# Driver_Message_Board.net
KiCad netlist of a schematic drawn in EAGLE
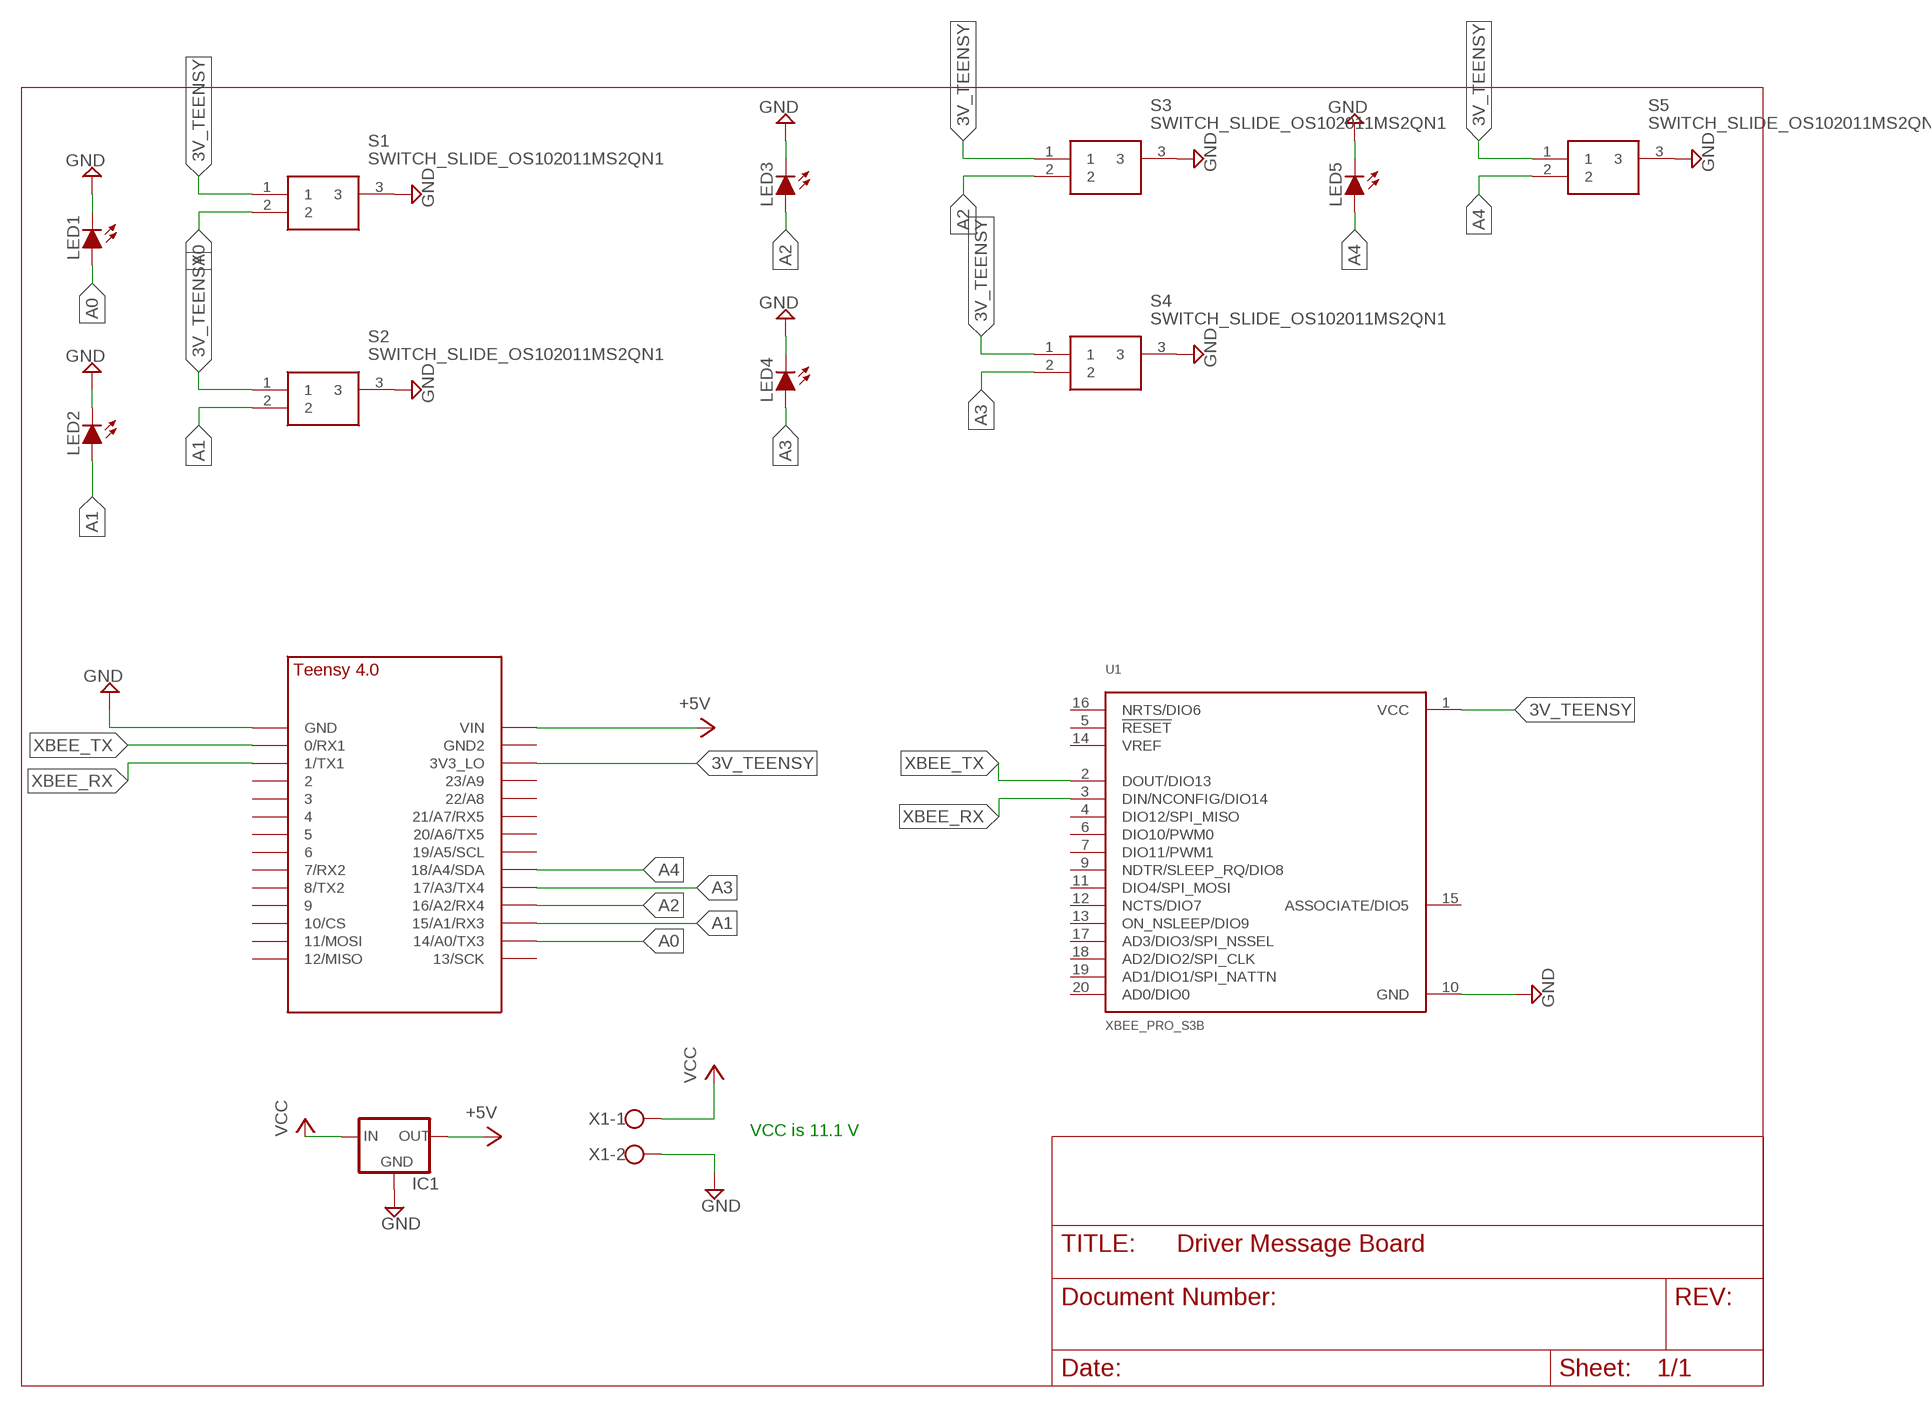
[diagram p0: schematic, sheet 1]

(export (version "E")
  (design (tool "Eeschema 10.0.6"))
  (components
    (comp (ref "IC1")
      (value "REG_5V_L7805_HOR_HOLE")
      (footprint "eagle-import:TO-220-H-HOLE")
      (libsource (lib "eagle-import") (part "REG_5V_L7805_HOR_HOLE"))
    )
    (comp (ref "LED1")
      (value "LED-5MM")
      (footprint "eagle-import:LED-5MM")
      (libsource (lib "eagle-import") (part "LED-5MM"))
    )
    (comp (ref "LED2")
      (value "LED-5MM")
      (footprint "eagle-import:LED-5MM")
      (libsource (lib "eagle-import") (part "LED-5MM"))
    )
    (comp (ref "LED3")
      (value "LED-5MM")
      (footprint "eagle-import:LED-5MM")
      (libsource (lib "eagle-import") (part "LED-5MM"))
    )
    (comp (ref "LED4")
      (value "LED-5MM")
      (footprint "eagle-import:LED-5MM")
      (libsource (lib "eagle-import") (part "LED-5MM"))
    )
    (comp (ref "LED5")
      (value "LED-5MM")
      (footprint "eagle-import:LED-5MM")
      (libsource (lib "eagle-import") (part "LED-5MM"))
    )
    (comp (ref "S1")
      (value "SWITCH_SLIDE_OS102011MS2QN1")
      (footprint "eagle-import:OS102011MA1QN1")
      (fields
        (field (name "ARROW_PART_NUMBER") "OS102011MS2QN1")
        (field (name "MOUSER_PART_NUMBER") "611-OS102011MS2QN1")
      )
      (libsource (lib "eagle-import") (part "SWITCH_SLIDE_OS102011MS2QN1"))
    )
    (comp (ref "S2")
      (value "SWITCH_SLIDE_OS102011MS2QN1")
      (footprint "eagle-import:OS102011MA1QN1")
      (fields
        (field (name "ARROW_PART_NUMBER") "OS102011MS2QN1")
        (field (name "MOUSER_PART_NUMBER") "611-OS102011MS2QN1")
      )
      (libsource (lib "eagle-import") (part "SWITCH_SLIDE_OS102011MS2QN1"))
    )
    (comp (ref "S3")
      (value "SWITCH_SLIDE_OS102011MS2QN1")
      (footprint "eagle-import:OS102011MA1QN1")
      (fields
        (field (name "ARROW_PART_NUMBER") "OS102011MS2QN1")
        (field (name "MOUSER_PART_NUMBER") "611-OS102011MS2QN1")
      )
      (libsource (lib "eagle-import") (part "SWITCH_SLIDE_OS102011MS2QN1"))
    )
    (comp (ref "S4")
      (value "SWITCH_SLIDE_OS102011MS2QN1")
      (footprint "eagle-import:OS102011MA1QN1")
      (fields
        (field (name "ARROW_PART_NUMBER") "OS102011MS2QN1")
        (field (name "MOUSER_PART_NUMBER") "611-OS102011MS2QN1")
      )
      (libsource (lib "eagle-import") (part "SWITCH_SLIDE_OS102011MS2QN1"))
    )
    (comp (ref "S5")
      (value "SWITCH_SLIDE_OS102011MS2QN1")
      (footprint "eagle-import:OS102011MA1QN1")
      (fields
        (field (name "ARROW_PART_NUMBER") "OS102011MS2QN1")
        (field (name "MOUSER_PART_NUMBER") "611-OS102011MS2QN1")
      )
      (libsource (lib "eagle-import") (part "SWITCH_SLIDE_OS102011MS2QN1"))
    )
    (comp (ref "U$1")
      (value "TEENSY_4.0_SIMPLE")
      (footprint "eagle-import:TEENSY_4.0_SIMPLE")
      (libsource (lib "eagle-import") (part "TEENSY_4.0_SIMPLE"))
    )
    (comp (ref "U1")
      (value "XBEE_PRO_S3B")
      (footprint "eagle-import:XBEE_PRO_S3B")
      (fields
        (field (name "DIGI-KEY_PART_NUMBER") "602-1293-ND")
        (field (name "MF") "Digi International")
        (field (name "MP") "XBP9B-XCST-001")
      )
      (libsource (lib "eagle-import") (part "XBEE_PRO_S3B"))
    )
    (comp (ref "X1")
      (value "W237-102")
      (footprint "eagle-import:W237-102")
      (fields (field (name "MPN") "237-102"))
      (libsource (lib "eagle-import") (part "W237-102"))
    )
  )
  (nets
    (net (code "1") (name "+5V") (class "Default")
      (node (ref "IC1") (pin "3") (pinfunction "OUT_3") (pintype "output"))
      (node (ref "U$1") (pin "VIN") (pinfunction "VIN_VIN") (pintype "bidirectional"))
    )
    (net (code "2") (name "3V_TEENSY") (class "Default")
      (node (ref "S1") (pin "1") (pinfunction "1_1") (pintype "bidirectional"))
      (node (ref "S2") (pin "1") (pinfunction "1_1") (pintype "bidirectional"))
      (node (ref "S3") (pin "1") (pinfunction "1_1") (pintype "bidirectional"))
      (node (ref "S4") (pin "1") (pinfunction "1_1") (pintype "bidirectional"))
      (node (ref "S5") (pin "1") (pinfunction "1_1") (pintype "bidirectional"))
      (node (ref "U$1") (pin "3V3_LO") (pinfunction "3V3_LO_3V3_LO") (pintype "bidirectional"))
      (node (ref "U1") (pin "1") (pinfunction "VCC_1") (pintype "power_in"))
    )
    (net (code "3") (name "A0") (class "Default")
      (node (ref "LED1") (pin "A") (pinfunction "A_A") (pintype "passive"))
      (node (ref "S1") (pin "2") (pinfunction "2_2") (pintype "bidirectional"))
      (node (ref "U$1") (pin "14/A0") (pinfunction "14/A0/TX3_14/A0") (pintype "bidirectional"))
    )
    (net (code "4") (name "A1") (class "Default")
      (node (ref "LED2") (pin "A") (pinfunction "A_A") (pintype "passive"))
      (node (ref "S2") (pin "2") (pinfunction "2_2") (pintype "bidirectional"))
      (node (ref "U$1") (pin "15/A1") (pinfunction "15/A1/RX3_15/A1") (pintype "bidirectional"))
    )
    (net (code "5") (name "A2") (class "Default")
      (node (ref "LED3") (pin "A") (pinfunction "A_A") (pintype "passive"))
      (node (ref "S3") (pin "2") (pinfunction "2_2") (pintype "bidirectional"))
      (node (ref "U$1") (pin "16/A2") (pinfunction "16/A2/RX4_16/A2") (pintype "bidirectional"))
    )
    (net (code "6") (name "A3") (class "Default")
      (node (ref "LED4") (pin "A") (pinfunction "A_A") (pintype "passive"))
      (node (ref "S4") (pin "2") (pinfunction "2_2") (pintype "bidirectional"))
      (node (ref "U$1") (pin "17/A3") (pinfunction "17/A3/TX4_17/A3") (pintype "bidirectional"))
    )
    (net (code "7") (name "A4") (class "Default")
      (node (ref "LED5") (pin "A") (pinfunction "A_A") (pintype "passive"))
      (node (ref "S5") (pin "2") (pinfunction "2_2") (pintype "bidirectional"))
      (node (ref "U$1") (pin "18/A4/SDA") (pinfunction "18/A4/SDA_18/A4/SDA") (pintype "bidirectional"))
    )
    (net (code "8") (name "GND") (class "Default")
      (node (ref "IC1") (pin "2") (pinfunction "GND_2") (pintype "input"))
      (node (ref "LED1") (pin "K") (pinfunction "C_K") (pintype "passive"))
      (node (ref "LED2") (pin "K") (pinfunction "C_K") (pintype "passive"))
      (node (ref "LED3") (pin "K") (pinfunction "C_K") (pintype "passive"))
      (node (ref "LED4") (pin "K") (pinfunction "C_K") (pintype "passive"))
      (node (ref "LED5") (pin "K") (pinfunction "C_K") (pintype "passive"))
      (node (ref "S1") (pin "3") (pinfunction "3_3") (pintype "bidirectional"))
      (node (ref "S2") (pin "3") (pinfunction "3_3") (pintype "bidirectional"))
      (node (ref "S3") (pin "3") (pinfunction "3_3") (pintype "bidirectional"))
      (node (ref "S4") (pin "3") (pinfunction "3_3") (pintype "bidirectional"))
      (node (ref "S5") (pin "3") (pinfunction "3_3") (pintype "bidirectional"))
      (node (ref "U$1") (pin "GND") (pinfunction "GND_GND") (pintype "bidirectional"))
      (node (ref "U1") (pin "10") (pinfunction "GND_10") (pintype "power_in"))
      (node (ref "X1") (pin "2") (pinfunction "KL_2") (pintype "passive"))
    )
    (net (code "9") (name "VCC") (class "Default")
      (node (ref "IC1") (pin "1") (pinfunction "IN_1") (pintype "input"))
      (node (ref "X1") (pin "1") (pinfunction "KL_1") (pintype "passive"))
    )
    (net (code "10") (name "XBEE_RX") (class "Default")
      (node (ref "U$1") (pin "1/TX") (pinfunction "1/TX1_1/TX") (pintype "bidirectional"))
      (node (ref "U1") (pin "3") (pinfunction "DIN/NCONFIG/DIO14_3") (pintype "bidirectional"))
    )
    (net (code "11") (name "XBEE_TX") (class "Default")
      (node (ref "U$1") (pin "0/RX") (pinfunction "0/RX1_0/RX") (pintype "bidirectional"))
      (node (ref "U1") (pin "2") (pinfunction "DOUT/DIO13_2") (pintype "bidirectional"))
    )
    (net (code "12") (name "unconnected-(U$1-3-Pad3{slash}CANTX)") (class "Default")
      (node (ref "U$1") (pin "3/CANTX") (pinfunction "3_3/CANTX") (pintype "bidirectional"))
    )
    (net (code "13") (name "unconnected-(U$1-4-Pad4{slash}CANRX)") (class "Default")
      (node (ref "U$1") (pin "4/CANRX") (pinfunction "4_4/CANRX") (pintype "bidirectional"))
    )
    (net (code "14") (name "unconnected-(U$1-7{slash}RX2-Pad7)") (class "Default")
      (node (ref "U$1") (pin "7") (pinfunction "7/RX2_7") (pintype "bidirectional"))
    )
    (net (code "15") (name "unconnected-(U$1-8{slash}TX2-Pad8)") (class "Default")
      (node (ref "U$1") (pin "8") (pinfunction "8/TX2_8") (pintype "bidirectional"))
    )
    (net (code "16") (name "unconnected-(U$1-9-Pad9{slash}CS)") (class "Default")
      (node (ref "U$1") (pin "9/CS") (pinfunction "9_9/CS") (pintype "bidirectional"))
    )
    (net (code "17") (name "unconnected-(U$1-20{slash}A6{slash}TX5-Pad20{slash}A6)") (class "Default")
      (node (ref "U$1") (pin "20/A6") (pinfunction "20/A6/TX5_20/A6") (pintype "bidirectional"))
    )
    (net (code "18") (name "unconnected-(U$1-21{slash}A7{slash}RX5-Pad21{slash}A7)") (class "Default")
      (node (ref "U$1") (pin "21/A7") (pinfunction "21/A7/RX5_21/A7") (pintype "bidirectional"))
    )
    (net (code "19") (name "unconnected-(U$1-Pad2)") (class "Default")
      (node (ref "U$1") (pin "2") (pinfunction "2_2") (pintype "bidirectional"))
    )
    (net (code "20") (name "unconnected-(U$1-Pad5)") (class "Default")
      (node (ref "U$1") (pin "5") (pinfunction "5_5") (pintype "bidirectional"))
    )
    (net (code "21") (name "unconnected-(U$1-Pad6)") (class "Default")
      (node (ref "U$1") (pin "6") (pinfunction "6_6") (pintype "bidirectional"))
    )
    (net (code "22") (name "unconnected-(U$1-Pad10{slash}CS)") (class "Default")
      (node (ref "U$1") (pin "10/CS") (pinfunction "10/CS_10/CS") (pintype "bidirectional"))
    )
    (net (code "23") (name "unconnected-(U$1-Pad11{slash}MOSI)") (class "Default")
      (node (ref "U$1") (pin "11/MOSI") (pinfunction "11/MOSI_11/MOSI") (pintype "bidirectional"))
    )
    (net (code "24") (name "unconnected-(U$1-Pad12{slash}MISO)") (class "Default")
      (node (ref "U$1") (pin "12/MISO") (pinfunction "12/MISO_12/MISO") (pintype "bidirectional"))
    )
    (net (code "25") (name "unconnected-(U$1-Pad13{slash}SCK)") (class "Default")
      (node (ref "U$1") (pin "13/SCK") (pinfunction "13/SCK_13/SCK") (pintype "bidirectional"))
    )
    (net (code "26") (name "unconnected-(U$1-Pad19{slash}A5{slash}SCL)") (class "Default")
      (node (ref "U$1") (pin "19/A5/SCL") (pinfunction "19/A5/SCL_19/A5/SCL") (pintype "bidirectional"))
    )
    (net (code "27") (name "unconnected-(U$1-Pad22{slash}A8)") (class "Default")
      (node (ref "U$1") (pin "22/A8") (pinfunction "22/A8_22/A8") (pintype "bidirectional"))
    )
    (net (code "28") (name "unconnected-(U$1-Pad23{slash}A9)") (class "Default")
      (node (ref "U$1") (pin "23/A9") (pinfunction "23/A9_23/A9") (pintype "bidirectional"))
    )
    (net (code "29") (name "unconnected-(U$1-PadGND2)") (class "Default")
      (node (ref "U$1") (pin "GND2") (pinfunction "GND2_GND2") (pintype "bidirectional"))
    )
    (net (code "30") (name "unconnected-(U1-AD0{slash}DIO0-Pad20)") (class "Default")
      (node (ref "U1") (pin "20") (pinfunction "AD0/DIO0_20") (pintype "bidirectional"))
    )
    (net (code "31") (name "unconnected-(U1-AD1{slash}DIO1{slash}SPI_NATTN-Pad19)") (class "Default")
      (node (ref "U1") (pin "19") (pinfunction "AD1/DIO1/SPI_NATTN_19") (pintype "bidirectional"))
    )
    (net (code "32") (name "unconnected-(U1-AD2{slash}DIO2{slash}SPI_CLK-Pad18)") (class "Default")
      (node (ref "U1") (pin "18") (pinfunction "AD2/DIO2/SPI_CLK_18") (pintype "bidirectional"))
    )
    (net (code "33") (name "unconnected-(U1-AD3{slash}DIO3{slash}SPI_NSSEL-Pad17)") (class "Default")
      (node (ref "U1") (pin "17") (pinfunction "AD3/DIO3/SPI_NSSEL_17") (pintype "bidirectional"))
    )
    (net (code "34") (name "unconnected-(U1-ASSOCIATE{slash}DIO5-Pad15)") (class "Default")
      (node (ref "U1") (pin "15") (pinfunction "ASSOCIATE/DIO5_15") (pintype "output"))
    )
    (net (code "35") (name "unconnected-(U1-DIO4{slash}SPI_MOSI-Pad11)") (class "Default")
      (node (ref "U1") (pin "11") (pinfunction "DIO4/SPI_MOSI_11") (pintype "bidirectional"))
    )
    (net (code "36") (name "unconnected-(U1-DIO10{slash}PWM0-Pad6)") (class "Default")
      (node (ref "U1") (pin "6") (pinfunction "DIO10/PWM0_6") (pintype "bidirectional"))
    )
    (net (code "37") (name "unconnected-(U1-DIO11{slash}PWM1-Pad7)") (class "Default")
      (node (ref "U1") (pin "7") (pinfunction "DIO11/PWM1_7") (pintype "bidirectional"))
    )
    (net (code "38") (name "unconnected-(U1-DIO12{slash}SPI_MISO-Pad4)") (class "Default")
      (node (ref "U1") (pin "4") (pinfunction "DIO12/SPI_MISO_4") (pintype "bidirectional"))
    )
    (net (code "39") (name "unconnected-(U1-NCTS{slash}DIO7-Pad12)") (class "Default")
      (node (ref "U1") (pin "12") (pinfunction "NCTS/DIO7_12") (pintype "bidirectional"))
    )
    (net (code "40") (name "unconnected-(U1-NDTR{slash}SLEEP_RQ{slash}DIO8-Pad9)") (class "Default")
      (node (ref "U1") (pin "9") (pinfunction "NDTR/SLEEP_RQ/DIO8_9") (pintype "bidirectional"))
    )
    (net (code "41") (name "unconnected-(U1-NRTS{slash}DIO6-Pad16)") (class "Default")
      (node (ref "U1") (pin "16") (pinfunction "NRTS/DIO6_16") (pintype "input"))
    )
    (net (code "42") (name "unconnected-(U1-ON_NSLEEP{slash}DIO9-Pad13)") (class "Default")
      (node (ref "U1") (pin "13") (pinfunction "ON_NSLEEP/DIO9_13") (pintype "bidirectional"))
    )
    (net (code "43") (name "unconnected-(U1-VREF-Pad14)") (class "Default")
      (node (ref "U1") (pin "14") (pinfunction "VREF_14") (pintype "input"))
    )
    (net (code "44") (name "unconnected-(U1-~{RESET}-Pad5)") (class "Default")
      (node (ref "U1") (pin "5") (pinfunction "~{RESET}_5") (pintype "input"))
    )
  )
)
